# audio_spectrum.net
KiCad netlist of a schematic drawn in EAGLE
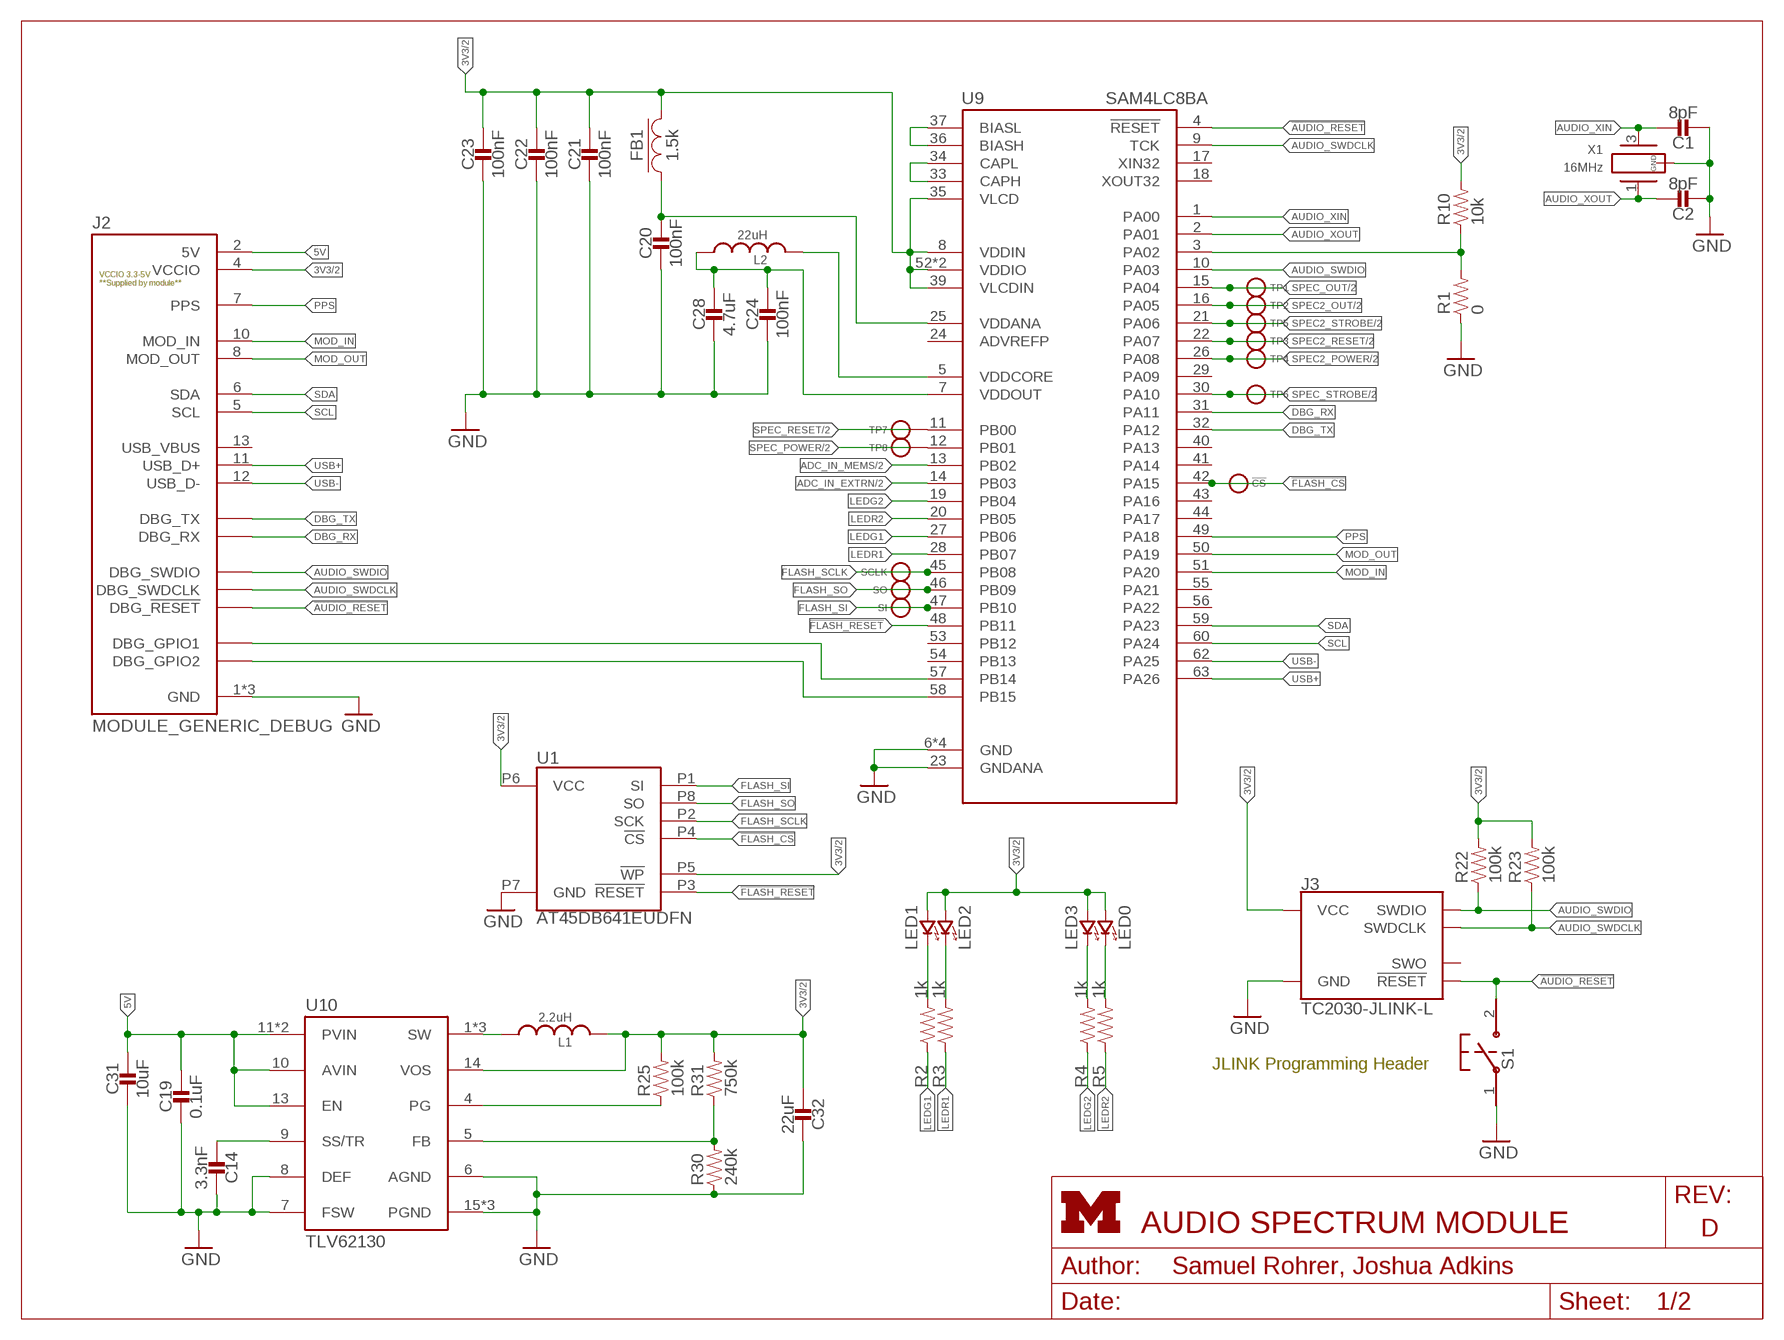
[diagram p0: schematic, sheet 1]
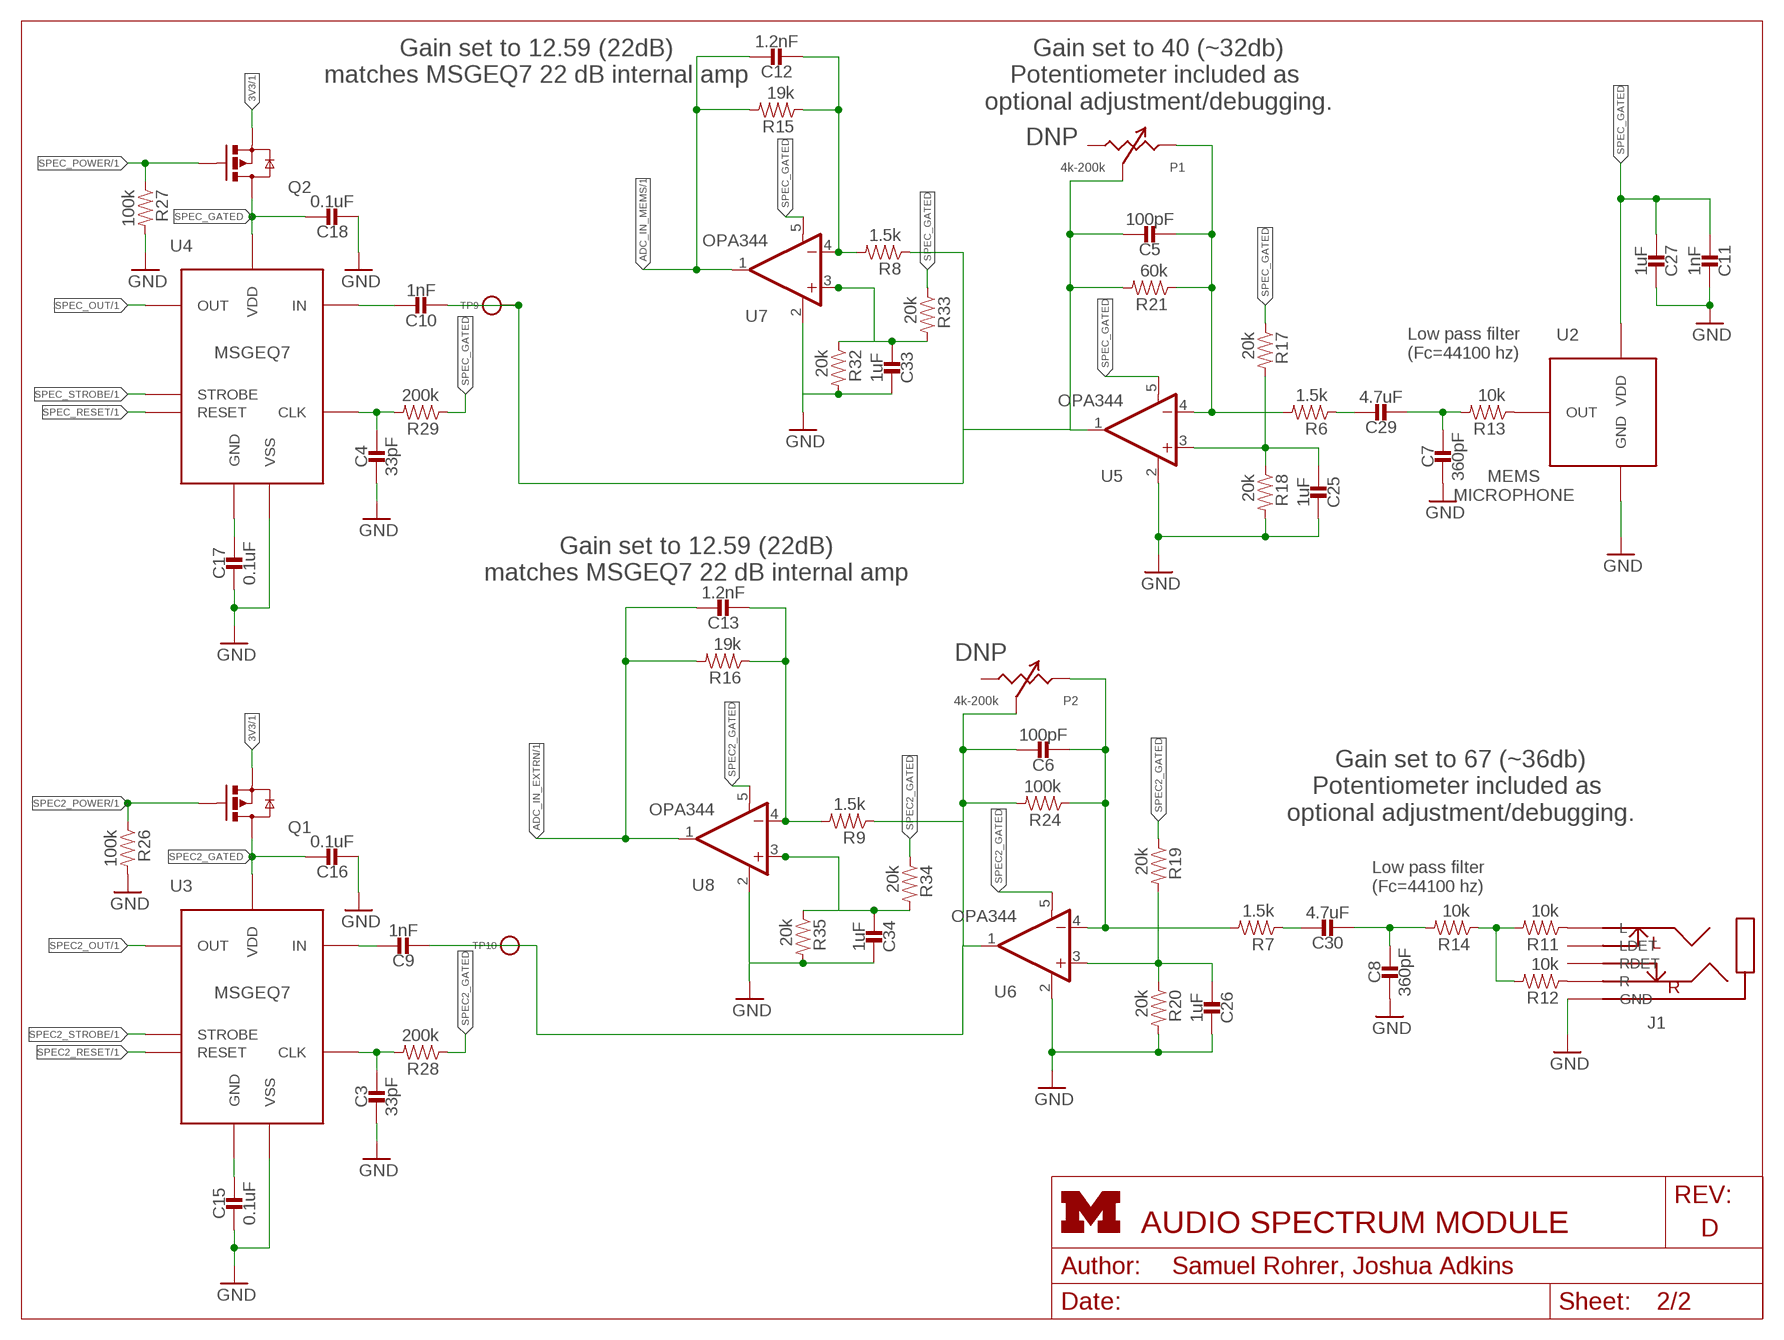
[diagram p1: schematic, sheet 2]

(export (version "E")
  (design (tool "Eeschema 10.0.6"))
  (components
    (comp (ref "C3")
      (value "33pF")
      (footprint "eagle-import:0603_CAP")
      (libsource (lib "eagle-import") (part "CAPACITOR0603_CAP"))
    )
    (comp (ref "C4")
      (value "33pF")
      (footprint "eagle-import:0603_CAP")
      (libsource (lib "eagle-import") (part "CAPACITOR0603_CAP"))
    )
    (comp (ref "C5")
      (value "100pF")
      (footprint "eagle-import:0603_CAP")
      (libsource (lib "eagle-import") (part "CAPACITOR0603_CAP"))
    )
    (comp (ref "C6")
      (value "100pF")
      (footprint "eagle-import:0603_CAP")
      (libsource (lib "eagle-import") (part "CAPACITOR0603_CAP"))
    )
    (comp (ref "C7")
      (value "360pF")
      (footprint "eagle-import:0603_CAP")
      (libsource (lib "eagle-import") (part "CAPACITOR0603_CAP"))
    )
    (comp (ref "C8")
      (value "360pF")
      (footprint "eagle-import:0603_CAP")
      (libsource (lib "eagle-import") (part "CAPACITOR0603_CAP"))
    )
    (comp (ref "C9")
      (value "1nF")
      (footprint "eagle-import:0603_CAP")
      (libsource (lib "eagle-import") (part "CAPACITOR0603_CAP"))
    )
    (comp (ref "C10")
      (value "1nF")
      (footprint "eagle-import:0603_CAP")
      (libsource (lib "eagle-import") (part "CAPACITOR0603_CAP"))
    )
    (comp (ref "C11")
      (value "1nF")
      (footprint "eagle-import:0603_CAP")
      (libsource (lib "eagle-import") (part "CAPACITOR0603_CAP"))
    )
    (comp (ref "C12")
      (value "1.2nF")
      (footprint "eagle-import:0603_CAP")
      (libsource (lib "eagle-import") (part "CAPACITOR0603_CAP"))
    )
    (comp (ref "C13")
      (value "1.2nF")
      (footprint "eagle-import:0603_CAP")
      (libsource (lib "eagle-import") (part "CAPACITOR0603_CAP"))
    )
    (comp (ref "C15")
      (value "0.1uF")
      (footprint "eagle-import:0603_CAP")
      (libsource (lib "eagle-import") (part "CAPACITOR0603_CAP"))
    )
    (comp (ref "C16")
      (value "0.1uF")
      (footprint "eagle-import:0603_CAP")
      (libsource (lib "eagle-import") (part "CAPACITOR0603_CAP"))
    )
    (comp (ref "C17")
      (value "0.1uF")
      (footprint "eagle-import:0603_CAP")
      (libsource (lib "eagle-import") (part "CAPACITOR0603_CAP"))
    )
    (comp (ref "C18")
      (value "0.1uF")
      (footprint "eagle-import:0603_CAP")
      (libsource (lib "eagle-import") (part "CAPACITOR0603_CAP"))
    )
    (comp (ref "C25")
      (value "1uF")
      (footprint "eagle-import:0603_CAP")
      (libsource (lib "eagle-import") (part "CAPACITOR0603_CAP"))
    )
    (comp (ref "C26")
      (value "1uF")
      (footprint "eagle-import:0603_CAP")
      (libsource (lib "eagle-import") (part "CAPACITOR0603_CAP"))
    )
    (comp (ref "C27")
      (value "1uF")
      (footprint "eagle-import:0603_CAP")
      (libsource (lib "eagle-import") (part "CAPACITOR0603_CAP"))
    )
    (comp (ref "C29")
      (value "4.7uF")
      (footprint "eagle-import:0603_CAP")
      (libsource (lib "eagle-import") (part "CAPACITOR0603_CAP"))
    )
    (comp (ref "C30")
      (value "4.7uF")
      (footprint "eagle-import:0603_CAP")
      (libsource (lib "eagle-import") (part "CAPACITOR0603_CAP"))
    )
    (comp (ref "C33")
      (value "1uF")
      (footprint "eagle-import:0603_CAP")
      (libsource (lib "eagle-import") (part "CAPACITOR0603_CAP"))
    )
    (comp (ref "C34")
      (value "1uF")
      (footprint "eagle-import:0603_CAP")
      (libsource (lib "eagle-import") (part "CAPACITOR0603_CAP"))
    )
    (comp (ref "J1")
      (value "AUDIO-JACK-VERTICAL")
      (footprint "eagle-import:AUDIO-JACK-VERTICAL")
      (libsource (lib "eagle-import") (part "AUDIO-JACK-VERTICAL"))
    )
    (comp (ref "P1")
      (value "4k-200k")
      (footprint "eagle-import:TC33X-2")
      (libsource (lib "eagle-import") (part "POTTC33X"))
    )
    (comp (ref "P2")
      (value "4k-200k")
      (footprint "eagle-import:TC33X-2")
      (libsource (lib "eagle-import") (part "POTTC33X"))
    )
    (comp (ref "Q1")
      (value "NX3008PBK")
      (footprint "eagle-import:SOT23-3")
      (libsource (lib "eagle-import") (part "NX3008PBK"))
    )
    (comp (ref "Q2")
      (value "NX3008PBK")
      (footprint "eagle-import:SOT23-3")
      (libsource (lib "eagle-import") (part "NX3008PBK"))
    )
    (comp (ref "R6")
      (value "1.5k")
      (footprint "eagle-import:0603-RES")
      (libsource (lib "eagle-import") (part "RESISTOR0603_RES"))
    )
    (comp (ref "R7")
      (value "1.5k")
      (footprint "eagle-import:0603-RES")
      (libsource (lib "eagle-import") (part "RESISTOR0603_RES"))
    )
    (comp (ref "R8")
      (value "1.5k")
      (footprint "eagle-import:0603-RES")
      (libsource (lib "eagle-import") (part "RESISTOR0603_RES"))
    )
    (comp (ref "R9")
      (value "1.5k")
      (footprint "eagle-import:0603-RES")
      (libsource (lib "eagle-import") (part "RESISTOR0603_RES"))
    )
    (comp (ref "R11")
      (value "10k")
      (footprint "eagle-import:0603-RES")
      (libsource (lib "eagle-import") (part "RESISTOR0603_RES"))
    )
    (comp (ref "R12")
      (value "10k")
      (footprint "eagle-import:0603-RES")
      (libsource (lib "eagle-import") (part "RESISTOR0603_RES"))
    )
    (comp (ref "R13")
      (value "10k")
      (footprint "eagle-import:0603-RES")
      (libsource (lib "eagle-import") (part "RESISTOR0603_RES"))
    )
    (comp (ref "R14")
      (value "10k")
      (footprint "eagle-import:0603-RES")
      (libsource (lib "eagle-import") (part "RESISTOR0603_RES"))
    )
    (comp (ref "R15")
      (value "19k")
      (footprint "eagle-import:0603-RES")
      (libsource (lib "eagle-import") (part "RESISTOR0603_RES"))
    )
    (comp (ref "R16")
      (value "19k")
      (footprint "eagle-import:0603-RES")
      (libsource (lib "eagle-import") (part "RESISTOR0603_RES"))
    )
    (comp (ref "R17")
      (value "20k")
      (footprint "eagle-import:0603-RES")
      (libsource (lib "eagle-import") (part "RESISTOR0603_RES"))
    )
    (comp (ref "R18")
      (value "20k")
      (footprint "eagle-import:0603-RES")
      (libsource (lib "eagle-import") (part "RESISTOR0603_RES"))
    )
    (comp (ref "R19")
      (value "20k")
      (footprint "eagle-import:0603-RES")
      (libsource (lib "eagle-import") (part "RESISTOR0603_RES"))
    )
    (comp (ref "R20")
      (value "20k")
      (footprint "eagle-import:0603-RES")
      (libsource (lib "eagle-import") (part "RESISTOR0603_RES"))
    )
    (comp (ref "R21")
      (value "60k")
      (footprint "eagle-import:0603-RES")
      (libsource (lib "eagle-import") (part "RESISTOR0603_RES"))
    )
    (comp (ref "R24")
      (value "100k")
      (footprint "eagle-import:0603-RES")
      (libsource (lib "eagle-import") (part "RESISTOR0603_RES"))
    )
    (comp (ref "R26")
      (value "100k")
      (footprint "eagle-import:0603-RES")
      (libsource (lib "eagle-import") (part "RESISTOR0603_RES"))
    )
    (comp (ref "R27")
      (value "100k")
      (footprint "eagle-import:0603-RES")
      (libsource (lib "eagle-import") (part "RESISTOR0603_RES"))
    )
    (comp (ref "R28")
      (value "200k")
      (footprint "eagle-import:0603-RES")
      (libsource (lib "eagle-import") (part "RESISTOR0603_RES"))
    )
    (comp (ref "R29")
      (value "200k")
      (footprint "eagle-import:0603-RES")
      (libsource (lib "eagle-import") (part "RESISTOR0603_RES"))
    )
    (comp (ref "R32")
      (value "20k")
      (footprint "eagle-import:0603-RES")
      (libsource (lib "eagle-import") (part "RESISTOR0603_RES"))
    )
    (comp (ref "R33")
      (value "20k")
      (footprint "eagle-import:0603-RES")
      (libsource (lib "eagle-import") (part "RESISTOR0603_RES"))
    )
    (comp (ref "R34")
      (value "20k")
      (footprint "eagle-import:0603-RES")
      (libsource (lib "eagle-import") (part "RESISTOR0603_RES"))
    )
    (comp (ref "R35")
      (value "20k")
      (footprint "eagle-import:0603-RES")
      (libsource (lib "eagle-import") (part "RESISTOR0603_RES"))
    )
    (comp (ref "TP9")
      (value "TEST_POINT_0.040IN")
      (footprint "eagle-import:TESTPOINT_0.040IN")
      (libsource (lib "eagle-import") (part "TEST_POINT_0.040IN"))
    )
    (comp (ref "TP10")
      (value "TEST_POINT_0.040IN")
      (footprint "eagle-import:TESTPOINT_0.040IN")
      (libsource (lib "eagle-import") (part "TEST_POINT_0.040IN"))
    )
    (comp (ref "U2")
      (value "MP23AB02B")
      (footprint "eagle-import:MP23AB02B")
      (libsource (lib "eagle-import") (part "MP23AB02B"))
    )
    (comp (ref "U3")
      (value "MSGEQ7")
      (footprint "eagle-import:DIP-8")
      (libsource (lib "eagle-import") (part "MSGEQ7"))
    )
    (comp (ref "U4")
      (value "MSGEQ7")
      (footprint "eagle-import:DIP-8")
      (libsource (lib "eagle-import") (part "MSGEQ7"))
    )
    (comp (ref "U5")
      (value "OPA344")
      (footprint "eagle-import:SOT23-5")
      (libsource (lib "eagle-import") (part "OPA344"))
    )
    (comp (ref "U6")
      (value "OPA344")
      (footprint "eagle-import:SOT23-5")
      (libsource (lib "eagle-import") (part "OPA344"))
    )
    (comp (ref "U7")
      (value "OPA344")
      (footprint "eagle-import:SOT23-5")
      (libsource (lib "eagle-import") (part "OPA344"))
    )
    (comp (ref "U8")
      (value "OPA344")
      (footprint "eagle-import:SOT23-5")
      (libsource (lib "eagle-import") (part "OPA344"))
    )
    (comp (ref "!CS")
      (value "TEST_POINT_0.040IN")
      (footprint "eagle-import:TESTPOINT_0.040IN")
      (libsource (lib "eagle-import") (part "TEST_POINT_0.040IN"))
    )
    (comp (ref "C1")
      (value "8pF")
      (footprint "eagle-import:0402_CAP")
      (libsource (lib "eagle-import") (part "CAPACITOR0402_CAP"))
    )
    (comp (ref "C2")
      (value "8pF")
      (footprint "eagle-import:0402_CAP")
      (libsource (lib "eagle-import") (part "CAPACITOR0402_CAP"))
    )
    (comp (ref "C14")
      (value "3.3nF")
      (footprint "eagle-import:0603_CAP")
      (libsource (lib "eagle-import") (part "CAPACITOR0603_CAP"))
    )
    (comp (ref "C19")
      (value "0.1uF")
      (footprint "eagle-import:0603_CAP")
      (libsource (lib "eagle-import") (part "CAPACITOR0603_CAP"))
    )
    (comp (ref "C20")
      (value "100nF")
      (footprint "eagle-import:0603_CAP")
      (libsource (lib "eagle-import") (part "CAPACITOR0603_CAP"))
    )
    (comp (ref "C21")
      (value "100nF")
      (footprint "eagle-import:0603_CAP")
      (libsource (lib "eagle-import") (part "CAPACITOR0603_CAP"))
    )
    (comp (ref "C22")
      (value "100nF")
      (footprint "eagle-import:0603_CAP")
      (libsource (lib "eagle-import") (part "CAPACITOR0603_CAP"))
    )
    (comp (ref "C23")
      (value "100nF")
      (footprint "eagle-import:0603_CAP")
      (libsource (lib "eagle-import") (part "CAPACITOR0603_CAP"))
    )
    (comp (ref "C24")
      (value "100nF")
      (footprint "eagle-import:0402_CAP")
      (libsource (lib "eagle-import") (part "CAPACITOR0402_CAP"))
    )
    (comp (ref "C28")
      (value "4.7uF")
      (footprint "eagle-import:0402_CAP")
      (libsource (lib "eagle-import") (part "CAPACITOR0402_CAP"))
    )
    (comp (ref "C31")
      (value "10uF")
      (footprint "eagle-import:0603_CAP")
      (libsource (lib "eagle-import") (part "CAPACITOR0603_CAP"))
    )
    (comp (ref "C32")
      (value "22uF")
      (footprint "eagle-import:0603_CAP")
      (libsource (lib "eagle-import") (part "CAPACITOR0603_CAP"))
    )
    (comp (ref "FB1")
      (value "1.5k")
      (footprint "eagle-import:0402_CAP")
      (libsource (lib "eagle-import") (part "FERRITE_BEAD0402"))
    )
    (comp (ref "J2")
      (value "MODULE_GENERIC_DEBUG")
      (footprint "eagle-import:MODULE_GENERIC_DEBUG")
      (libsource (lib "eagle-import") (part "MODULE_GENERIC_DEBUG"))
    )
    (comp (ref "J3")
      (value "TC2030-JLINK-L")
      (footprint "eagle-import:TC2030-IDC")
      (libsource (lib "eagle-import") (part "TC2030-JLINK-L"))
    )
    (comp (ref "L1")
      (value "2.2uH")
      (footprint "eagle-import:IHL-1212BZ-11")
      (libsource (lib "eagle-import") (part "INDUCTORIHL"))
    )
    (comp (ref "L2")
      (value "22uH")
      (footprint "eagle-import:1212")
      (libsource (lib "eagle-import") (part "LHQ3NP"))
    )
    (comp (ref "LED0")
      (value "LED0603")
      (footprint "eagle-import:LED-0603")
      (libsource (lib "eagle-import") (part "LED0603"))
    )
    (comp (ref "LED1")
      (value "LED0603")
      (footprint "eagle-import:LED-0603")
      (libsource (lib "eagle-import") (part "LED0603"))
    )
    (comp (ref "LED2")
      (value "LED0603")
      (footprint "eagle-import:LED-0603")
      (libsource (lib "eagle-import") (part "LED0603"))
    )
    (comp (ref "LED3")
      (value "LED0603")
      (footprint "eagle-import:LED-0603")
      (libsource (lib "eagle-import") (part "LED0603"))
    )
    (comp (ref "R1")
      (value "0")
      (footprint "eagle-import:0603-RES")
      (libsource (lib "eagle-import") (part "RESISTOR0603_RES"))
    )
    (comp (ref "R2")
      (value "1k")
      (footprint "eagle-import:0603-RES")
      (libsource (lib "eagle-import") (part "RESISTOR0603_RES"))
    )
    (comp (ref "R3")
      (value "1k")
      (footprint "eagle-import:0603-RES")
      (libsource (lib "eagle-import") (part "RESISTOR0603_RES"))
    )
    (comp (ref "R4")
      (value "1k")
      (footprint "eagle-import:0603-RES")
      (libsource (lib "eagle-import") (part "RESISTOR0603_RES"))
    )
    (comp (ref "R5")
      (value "1k")
      (footprint "eagle-import:0603-RES")
      (libsource (lib "eagle-import") (part "RESISTOR0603_RES"))
    )
    (comp (ref "R10")
      (value "10k")
      (footprint "eagle-import:0603-RES")
      (libsource (lib "eagle-import") (part "RESISTOR0603_RES"))
    )
    (comp (ref "R22")
      (value "100k")
      (footprint "eagle-import:0603-RES")
      (libsource (lib "eagle-import") (part "RESISTOR0603_RES"))
    )
    (comp (ref "R23")
      (value "100k")
      (footprint "eagle-import:0603-RES")
      (libsource (lib "eagle-import") (part "RESISTOR0603_RES"))
    )
    (comp (ref "R25")
      (value "100k")
      (footprint "eagle-import:0603-RES")
      (libsource (lib "eagle-import") (part "RESISTOR0603_RES"))
    )
    (comp (ref "R30")
      (value "240k")
      (footprint "eagle-import:0603-RES")
      (libsource (lib "eagle-import") (part "RESISTOR0603_RES"))
    )
    (comp (ref "R31")
      (value "750k")
      (footprint "eagle-import:0603-RES")
      (libsource (lib "eagle-import") (part "RESISTOR0603_RES"))
    )
    (comp (ref "S1")
      (value "B3U-1000P")
      (footprint "eagle-import:B3U-1000P")
      (libsource (lib "eagle-import") (part "B3U-1000P"))
    )
    (comp (ref "SCLK")
      (value "TEST_POINT_0.040IN")
      (footprint "eagle-import:TESTPOINT_0.040IN")
      (libsource (lib "eagle-import") (part "TEST_POINT_0.040IN"))
    )
    (comp (ref "SI")
      (value "TEST_POINT_0.040IN")
      (footprint "eagle-import:TESTPOINT_0.040IN")
      (libsource (lib "eagle-import") (part "TEST_POINT_0.040IN"))
    )
    (comp (ref "SO")
      (value "TEST_POINT_0.040IN")
      (footprint "eagle-import:TESTPOINT_0.040IN")
      (libsource (lib "eagle-import") (part "TEST_POINT_0.040IN"))
    )
    (comp (ref "TP1")
      (value "TEST_POINT_0.040IN")
      (footprint "eagle-import:TESTPOINT_0.040IN")
      (libsource (lib "eagle-import") (part "TEST_POINT_0.040IN"))
    )
    (comp (ref "TP2")
      (value "TEST_POINT_0.040IN")
      (footprint "eagle-import:TESTPOINT_0.040IN")
      (libsource (lib "eagle-import") (part "TEST_POINT_0.040IN"))
    )
    (comp (ref "TP3")
      (value "TEST_POINT_0.040IN")
      (footprint "eagle-import:TESTPOINT_0.040IN")
      (libsource (lib "eagle-import") (part "TEST_POINT_0.040IN"))
    )
    (comp (ref "TP4")
      (value "TEST_POINT_0.040IN")
      (footprint "eagle-import:TESTPOINT_0.040IN")
      (libsource (lib "eagle-import") (part "TEST_POINT_0.040IN"))
    )
    (comp (ref "TP5")
      (value "TEST_POINT_0.040IN")
      (footprint "eagle-import:TESTPOINT_0.040IN")
      (libsource (lib "eagle-import") (part "TEST_POINT_0.040IN"))
    )
    (comp (ref "TP6")
      (value "TEST_POINT_0.040IN")
      (footprint "eagle-import:TESTPOINT_0.040IN")
      (libsource (lib "eagle-import") (part "TEST_POINT_0.040IN"))
    )
    (comp (ref "TP7")
      (value "TEST_POINT_0.040IN")
      (footprint "eagle-import:TESTPOINT_0.040IN")
      (libsource (lib "eagle-import") (part "TEST_POINT_0.040IN"))
    )
    (comp (ref "TP8")
      (value "TEST_POINT_0.040IN")
      (footprint "eagle-import:TESTPOINT_0.040IN")
      (libsource (lib "eagle-import") (part "TEST_POINT_0.040IN"))
    )
    (comp (ref "U1")
      (value "AT45DB641EUDFN")
      (footprint "eagle-import:UDFN-8-5MMX6MM")
      (libsource (lib "eagle-import") (part "AT45DB641EUDFN"))
    )
    (comp (ref "U9")
      (value "SAM4LC8BA")
      (footprint "eagle-import:QFN-64-9MM")
      (libsource (lib "eagle-import") (part "SAM4LC8BA"))
    )
    (comp (ref "U10")
      (value "TLV62130")
      (footprint "eagle-import:TQFN-16_3MM")
      (libsource (lib "eagle-import") (part "TLV62130"))
    )
    (comp (ref "X1")
      (value "16MHz")
      (footprint "eagle-import:FHXXX")
      (libsource (lib "eagle-import") (part "FH1600015"))
    )
  )
  (nets
    (net (code "1") (name "3V3") (class "Default")
      (node (ref "C21") (pin "1") (pinfunction "1_1") (pintype "bidirectional"))
      (node (ref "C22") (pin "1") (pinfunction "1_1") (pintype "bidirectional"))
      (node (ref "C23") (pin "1") (pinfunction "1_1") (pintype "bidirectional"))
      (node (ref "C32") (pin "2") (pinfunction "2_2") (pintype "bidirectional"))
      (node (ref "FB1") (pin "2") (pinfunction "P$2_2") (pintype "bidirectional"))
      (node (ref "J2") (pin "4") (pinfunction "VCCIO_4") (pintype "bidirectional"))
      (node (ref "J3") (pin "1") (pinfunction "VCC_1") (pintype "bidirectional"))
      (node (ref "L1") (pin "P$2") (pinfunction "2_P$2") (pintype "bidirectional"))
      (node (ref "LED0") (pin "A") (pinfunction "ANODE_A") (pintype "bidirectional"))
      (node (ref "LED1") (pin "A") (pinfunction "ANODE_A") (pintype "bidirectional"))
      (node (ref "LED2") (pin "A") (pinfunction "ANODE_A") (pintype "bidirectional"))
      (node (ref "LED3") (pin "A") (pinfunction "ANODE_A") (pintype "bidirectional"))
      (node (ref "Q1") (pin "2") (pinfunction "S_2") (pintype "passive"))
      (node (ref "Q2") (pin "2") (pinfunction "S_2") (pintype "passive"))
      (node (ref "R10") (pin "2") (pinfunction "2_2") (pintype "passive"))
      (node (ref "R22") (pin "2") (pinfunction "2_2") (pintype "passive"))
      (node (ref "R23") (pin "2") (pinfunction "2_2") (pintype "passive"))
      (node (ref "R25") (pin "2") (pinfunction "2_2") (pintype "passive"))
      (node (ref "R31") (pin "2") (pinfunction "2_2") (pintype "passive"))
      (node (ref "U1") (pin "P5") (pinfunction "~{WP}_P5") (pintype "bidirectional"))
      (node (ref "U1") (pin "P6") (pinfunction "VCC_P6") (pintype "bidirectional"))
      (node (ref "U10") (pin "14") (pinfunction "VOS_14") (pintype "bidirectional"))
      (node (ref "U9") (pin "35") (pinfunction "VLCD_35") (pintype "bidirectional"))
      (node (ref "U9") (pin "39") (pinfunction "VLCDIN_39") (pintype "power_in"))
      (node (ref "U9") (pin "52") (pinfunction "VDDIO_52") (pintype "power_in"))
      (node (ref "U9") (pin "61") (pinfunction "VDDIO_61") (pintype "power_in"))
      (node (ref "U9") (pin "8") (pinfunction "VDDIN_8") (pintype "power_in"))
    )
    (net (code "2") (name "5V") (class "Default")
      (node (ref "C19") (pin "1") (pinfunction "1_1") (pintype "bidirectional"))
      (node (ref "C31") (pin "1") (pinfunction "1_1") (pintype "bidirectional"))
      (node (ref "J2") (pin "2") (pinfunction "5V_2") (pintype "bidirectional"))
      (node (ref "U10") (pin "10") (pinfunction "AVIN_10") (pintype "bidirectional"))
      (node (ref "U10") (pin "11") (pinfunction "PVIN_11") (pintype "bidirectional"))
      (node (ref "U10") (pin "12") (pinfunction "PVIN_12") (pintype "bidirectional"))
      (node (ref "U10") (pin "13") (pinfunction "EN_13") (pintype "bidirectional"))
    )
    (net (code "3") (name "ADC_IN_EXTRN") (class "Default")
      (node (ref "C13") (pin "1") (pinfunction "1_1") (pintype "bidirectional"))
      (node (ref "R16") (pin "2") (pinfunction "2_2") (pintype "passive"))
      (node (ref "U8") (pin "1") (pinfunction "OUT_1") (pintype "output"))
      (node (ref "U9") (pin "14") (pinfunction "PB03_14") (pintype "bidirectional"))
    )
    (net (code "4") (name "ADC_IN_MEMS") (class "Default")
      (node (ref "C12") (pin "1") (pinfunction "1_1") (pintype "bidirectional"))
      (node (ref "R15") (pin "2") (pinfunction "2_2") (pintype "passive"))
      (node (ref "U7") (pin "1") (pinfunction "OUT_1") (pintype "output"))
      (node (ref "U9") (pin "13") (pinfunction "PB02_13") (pintype "bidirectional"))
    )
    (net (code "5") (name "AUDIO_SWDCLK") (class "Default")
      (node (ref "J2") (pin "21") (pinfunction "DBG_SWDCLK_21") (pintype "bidirectional"))
      (node (ref "J3") (pin "4") (pinfunction "SWDCLK_4") (pintype "bidirectional"))
      (node (ref "R23") (pin "1") (pinfunction "1_1") (pintype "passive"))
      (node (ref "U9") (pin "9") (pinfunction "TCK_9") (pintype "bidirectional"))
    )
    (net (code "6") (name "AUDIO_SWDIO") (class "Default")
      (node (ref "J2") (pin "22") (pinfunction "DBG_SWDIO_22") (pintype "bidirectional"))
      (node (ref "J3") (pin "2") (pinfunction "SWDIO_2") (pintype "bidirectional"))
      (node (ref "R22") (pin "1") (pinfunction "1_1") (pintype "passive"))
      (node (ref "U9") (pin "10") (pinfunction "PA03_10") (pintype "bidirectional"))
    )
    (net (code "7") (name "AUDIO_XIN") (class "Default")
      (node (ref "C1") (pin "1") (pinfunction "1_1") (pintype "bidirectional"))
      (node (ref "U9") (pin "1") (pinfunction "PA00_1") (pintype "bidirectional"))
      (node (ref "X1") (pin "3") (pinfunction "2_3") (pintype "bidirectional"))
    )
    (net (code "8") (name "AUDIO_XOUT") (class "Default")
      (node (ref "C2") (pin "1") (pinfunction "1_1") (pintype "bidirectional"))
      (node (ref "U9") (pin "2") (pinfunction "PA01_2") (pintype "bidirectional"))
      (node (ref "X1") (pin "1") (pinfunction "1_1") (pintype "bidirectional"))
    )
    (net (code "9") (name "DBG_RX") (class "Default")
      (node (ref "J2") (pin "18") (pinfunction "DBG_RX_18") (pintype "bidirectional"))
      (node (ref "U9") (pin "31") (pinfunction "PA11_31") (pintype "bidirectional"))
    )
    (net (code "10") (name "DBG_TX") (class "Default")
      (node (ref "J2") (pin "17") (pinfunction "DBG_TX_17") (pintype "bidirectional"))
      (node (ref "U9") (pin "32") (pinfunction "PA12_32") (pintype "bidirectional"))
    )
    (net (code "11") (name "FLASH_SCLK") (class "Default")
      (node (ref "SCLK") (pin "TESTPOINT") (pinfunction "TESTPOINT_TESTPOINT") (pintype "bidirectional"))
      (node (ref "U1") (pin "P2") (pinfunction "SCK_P2") (pintype "bidirectional"))
      (node (ref "U9") (pin "45") (pinfunction "PB08_45") (pintype "bidirectional"))
    )
    (net (code "12") (name "FLASH_SI") (class "Default")
      (node (ref "SI") (pin "TESTPOINT") (pinfunction "TESTPOINT_TESTPOINT") (pintype "bidirectional"))
      (node (ref "U1") (pin "P1") (pinfunction "SI_P1") (pintype "bidirectional"))
      (node (ref "U9") (pin "47") (pinfunction "PB10_47") (pintype "bidirectional"))
    )
    (net (code "13") (name "FLASH_SO") (class "Default")
      (node (ref "SO") (pin "TESTPOINT") (pinfunction "TESTPOINT_TESTPOINT") (pintype "bidirectional"))
      (node (ref "U1") (pin "P8") (pinfunction "SO_P8") (pintype "bidirectional"))
      (node (ref "U9") (pin "46") (pinfunction "PB09_46") (pintype "bidirectional"))
    )
    (net (code "14") (name "GND") (class "Default")
      (node (ref "C1") (pin "2") (pinfunction "2_2") (pintype "bidirectional"))
      (node (ref "C11") (pin "1") (pinfunction "1_1") (pintype "bidirectional"))
      (node (ref "C14") (pin "1") (pinfunction "1_1") (pintype "bidirectional"))
      (node (ref "C15") (pin "2") (pinfunction "2_2") (pintype "bidirectional"))
      (node (ref "C16") (pin "2") (pinfunction "2_2") (pintype "bidirectional"))
      (node (ref "C17") (pin "2") (pinfunction "2_2") (pintype "bidirectional"))
      (node (ref "C18") (pin "2") (pinfunction "2_2") (pintype "bidirectional"))
      (node (ref "C19") (pin "2") (pinfunction "2_2") (pintype "bidirectional"))
      (node (ref "C2") (pin "2") (pinfunction "2_2") (pintype "bidirectional"))
      (node (ref "C20") (pin "2") (pinfunction "2_2") (pintype "bidirectional"))
      (node (ref "C21") (pin "2") (pinfunction "2_2") (pintype "bidirectional"))
      (node (ref "C22") (pin "2") (pinfunction "2_2") (pintype "bidirectional"))
      (node (ref "C23") (pin "2") (pinfunction "2_2") (pintype "bidirectional"))
      (node (ref "C24") (pin "2") (pinfunction "2_2") (pintype "bidirectional"))
      (node (ref "C25") (pin "1") (pinfunction "1_1") (pintype "bidirectional"))
      (node (ref "C26") (pin "1") (pinfunction "1_1") (pintype "bidirectional"))
      (node (ref "C27") (pin "1") (pinfunction "1_1") (pintype "bidirectional"))
      (node (ref "C28") (pin "2") (pinfunction "2_2") (pintype "bidirectional"))
      (node (ref "C3") (pin "2") (pinfunction "2_2") (pintype "bidirectional"))
      (node (ref "C31") (pin "2") (pinfunction "2_2") (pintype "bidirectional"))
      (node (ref "C32") (pin "1") (pinfunction "1_1") (pintype "bidirectional"))
      (node (ref "C33") (pin "1") (pinfunction "1_1") (pintype "bidirectional"))
      (node (ref "C34") (pin "1") (pinfunction "1_1") (pintype "bidirectional"))
      (node (ref "C4") (pin "2") (pinfunction "2_2") (pintype "bidirectional"))
      (node (ref "C7") (pin "2") (pinfunction "2_2") (pintype "bidirectional"))
      (node (ref "C8") (pin "2") (pinfunction "2_2") (pintype "bidirectional"))
      (node (ref "J1") (pin "5") (pinfunction "GND_5") (pintype "bidirectional"))
      (node (ref "J2") (pin "1") (pinfunction "GND_1") (pintype "bidirectional"))
      (node (ref "J2") (pin "14") (pinfunction "GND_14") (pintype "bidirectional"))
      (node (ref "J2") (pin "15") (pinfunction "GND_15") (pintype "bidirectional"))
      (node (ref "J3") (pin "5") (pinfunction "GND_5") (pintype "bidirectional"))
      (node (ref "R1") (pin "1") (pinfunction "1_1") (pintype "passive"))
      (node (ref "R18") (pin "2") (pinfunction "2_2") (pintype "passive"))
      (node (ref "R20") (pin "2") (pinfunction "2_2") (pintype "passive"))
      (node (ref "R26") (pin "2") (pinfunction "2_2") (pintype "passive"))
      (node (ref "R27") (pin "2") (pinfunction "2_2") (pintype "passive"))
      (node (ref "R30") (pin "1") (pinfunction "1_1") (pintype "passive"))
      (node (ref "R32") (pin "2") (pinfunction "2_2") (pintype "passive"))
      (node (ref "R35") (pin "2") (pinfunction "2_2") (pintype "passive"))
      (node (ref "S1") (pin "1") (pinfunction "P$1_1") (pintype "passive"))
      (node (ref "U1") (pin "P7") (pinfunction "GND_P7") (pintype "bidirectional"))
      (node (ref "U10") (pin "15") (pinfunction "PGND_15") (pintype "bidirectional"))
      (node (ref "U10") (pin "16") (pinfunction "PGND_16") (pintype "bidirectional"))
      (node (ref "U10") (pin "6") (pinfunction "AGND_6") (pintype "bidirectional"))
      (node (ref "U10") (pin "7") (pinfunction "FSW_7") (pintype "bidirectional"))
      (node (ref "U10") (pin "8") (pinfunction "DEF_8") (pintype "bidirectional"))
      (node (ref "U10") (pin "GND") (pinfunction "PGND_GND") (pintype "bidirectional"))
      (node (ref "U2") (pin "3") (pinfunction "GND_3") (pintype "bidirectional"))
      (node (ref "U3") (pin "2") (pinfunction "VSS_2") (pintype "bidirectional"))
      (node (ref "U4") (pin "2") (pinfunction "VSS_2") (pintype "bidirectional"))
      (node (ref "U5") (pin "2") (pinfunction "V-_2") (pintype "power_in"))
      (node (ref "U6") (pin "2") (pinfunction "V-_2") (pintype "power_in"))
      (node (ref "U7") (pin "2") (pinfunction "V-_2") (pintype "power_in"))
      (node (ref "U8") (pin "2") (pinfunction "V-_2") (pintype "power_in"))
      (node (ref "U9") (pin "23") (pinfunction "GNDANA_23") (pintype "power_in"))
      (node (ref "U9") (pin "38") (pinfunction "GND_38") (pintype "power_in"))
      (node (ref "U9") (pin "6") (pinfunction "GND_6") (pintype "power_in"))
      (node (ref "U9") (pin "64") (pinfunction "GND_64") (pintype "power_in"))
      (node (ref "U9") (pin "GND") (pinfunction "GND_GND") (pintype "power_in"))
      (node (ref "X1") (pin "2") (pinfunction "GND_2") (pintype "bidirectional"))
      (node (ref "X1") (pin "4") (pinfunction "GND_4") (pintype "bidirectional"))
    )
    (net (code "15") (name "LEDG1") (class "Default")
      (node (ref "R2") (pin "1") (pinfunction "1_1") (pintype "passive"))
      (node (ref "U9") (pin "27") (pinfunction "PB06_27") (pintype "bidirectional"))
    )
    (net (code "16") (name "LEDG2") (class "Default")
      (node (ref "R4") (pin "1") (pinfunction "1_1") (pintype "passive"))
      (node (ref "U9") (pin "19") (pinfunction "PB04_19") (pintype "bidirectional"))
    )
    (net (code "17") (name "LEDR1") (class "Default")
      (node (ref "R3") (pin "1") (pinfunction "1_1") (pintype "passive"))
      (node (ref "U9") (pin "28") (pinfunction "PB07_28") (pintype "bidirectional"))
    )
    (net (code "18") (name "LEDR2") (class "Default")
      (node (ref "R5") (pin "1") (pinfunction "1_1") (pintype "passive"))
      (node (ref "U9") (pin "20") (pinfunction "PB05_20") (pintype "bidirectional"))
    )
    (net (code "19") (name "MOD_IN") (class "Default")
      (node (ref "J2") (pin "10") (pinfunction "MOD_IN_10") (pintype "bidirectional"))
      (node (ref "U9") (pin "51") (pinfunction "PA20_51") (pintype "bidirectional"))
    )
    (net (code "20") (name "MOD_OUT") (class "Default")
      (node (ref "J2") (pin "8") (pinfunction "MOD_OUT_8") (pintype "bidirectional"))
      (node (ref "U9") (pin "50") (pinfunction "PA19_50") (pintype "bidirectional"))
    )
    (net (code "21") (name "Net-(C29-Pad1)") (class "Default")
      (node (ref "C29") (pin "1") (pinfunction "1_1") (pintype "bidirectional"))
      (node (ref "R6") (pin "1") (pinfunction "1_1") (pintype "passive"))
    )
    (net (code "22") (name "Net-(C29-Pad2)") (class "Default")
      (node (ref "C29") (pin "2") (pinfunction "2_2") (pintype "bidirectional"))
      (node (ref "C7") (pin "1") (pinfunction "1_1") (pintype "bidirectional"))
      (node (ref "R13") (pin "2") (pinfunction "2_2") (pintype "passive"))
    )
    (net (code "23") (name "Net-(C30-Pad1)") (class "Default")
      (node (ref "C30") (pin "1") (pinfunction "1_1") (pintype "bidirectional"))
      (node (ref "R7") (pin "1") (pinfunction "1_1") (pintype "passive"))
    )
    (net (code "24") (name "Net-(C30-Pad2)") (class "Default")
      (node (ref "C30") (pin "2") (pinfunction "2_2") (pintype "bidirectional"))
      (node (ref "C8") (pin "1") (pinfunction "1_1") (pintype "bidirectional"))
      (node (ref "R14") (pin "2") (pinfunction "2_2") (pintype "passive"))
    )
    (net (code "25") (name "Net-(FB1-P$1)") (class "Default")
      (node (ref "C20") (pin "1") (pinfunction "1_1") (pintype "bidirectional"))
      (node (ref "FB1") (pin "1") (pinfunction "P$1_1") (pintype "bidirectional"))
      (node (ref "U9") (pin "25") (pinfunction "VDDANA_25") (pintype "power_in"))
    )
    (net (code "26") (name "Net-(J1-L)") (class "Default")
      (node (ref "J1") (pin "4") (pinfunction "L_4") (pintype "bidirectional"))
      (node (ref "R11") (pin "1") (pinfunction "1_1") (pintype "passive"))
    )
    (net (code "27") (name "Net-(J1-R)") (class "Default")
      (node (ref "J1") (pin "1") (pinfunction "R_1") (pintype "bidirectional"))
      (node (ref "R12") (pin "1") (pinfunction "1_1") (pintype "passive"))
    )
    (net (code "28") (name "Net-(J2-DBG_GPIO1)") (class "Default")
      (node (ref "J2") (pin "16") (pinfunction "DBG_GPIO1_16") (pintype "bidirectional"))
      (node (ref "U9") (pin "57") (pinfunction "PB14_57") (pintype "bidirectional"))
    )
    (net (code "29") (name "Net-(J2-DBG_GPIO2)") (class "Default")
      (node (ref "J2") (pin "19") (pinfunction "DBG_GPIO2_19") (pintype "bidirectional"))
      (node (ref "U9") (pin "58") (pinfunction "PB15_58") (pintype "bidirectional"))
    )
    (net (code "30") (name "Net-(L1-1)") (class "Default")
      (node (ref "L1") (pin "P$1") (pinfunction "1_P$1") (pintype "bidirectional"))
      (node (ref "U10") (pin "1") (pinfunction "SW_1") (pintype "bidirectional"))
      (node (ref "U10") (pin "2") (pinfunction "SW_2") (pintype "bidirectional"))
      (node (ref "U10") (pin "3") (pinfunction "SW_3") (pintype "bidirectional"))
    )
    (net (code "31") (name "Net-(L2-1)") (class "Default")
      (node (ref "C24") (pin "1") (pinfunction "1_1") (pintype "bidirectional"))
      (node (ref "C28") (pin "1") (pinfunction "1_1") (pintype "bidirectional"))
      (node (ref "L2") (pin "P$1") (pinfunction "1_P$1") (pintype "bidirectional"))
      (node (ref "U9") (pin "7") (pinfunction "VDDOUT_7") (pintype "power_in"))
    )
    (net (code "32") (name "Net-(L2-2)") (class "Default")
      (node (ref "L2") (pin "P$2") (pinfunction "2_P$2") (pintype "bidirectional"))
      (node (ref "U9") (pin "5") (pinfunction "VDDCORE_5") (pintype "power_in"))
    )
    (net (code "33") (name "Net-(LED0-CATHODE)") (class "Default")
      (node (ref "LED0") (pin "C") (pinfunction "CATHODE_C") (pintype "bidirectional"))
      (node (ref "R5") (pin "2") (pinfunction "2_2") (pintype "passive"))
    )
    (net (code "34") (name "Net-(LED1-CATHODE)") (class "Default")
      (node (ref "LED1") (pin "C") (pinfunction "CATHODE_C") (pintype "bidirectional"))
      (node (ref "R2") (pin "2") (pinfunction "2_2") (pintype "passive"))
    )
    (net (code "35") (name "Net-(LED2-CATHODE)") (class "Default")
      (node (ref "LED2") (pin "C") (pinfunction "CATHODE_C") (pintype "bidirectional"))
      (node (ref "R3") (pin "2") (pinfunction "2_2") (pintype "passive"))
    )
    (net (code "36") (name "Net-(LED3-CATHODE)") (class "Default")
      (node (ref "LED3") (pin "C") (pinfunction "CATHODE_C") (pintype "bidirectional"))
      (node (ref "R4") (pin "2") (pinfunction "2_2") (pintype "passive"))
    )
    (net (code "37") (name "Net-(P1-CW)") (class "Default")
      (node (ref "C5") (pin "2") (pinfunction "2_2") (pintype "bidirectional"))
      (node (ref "P1") (pin "2") (pinfunction "CW_2") (pintype "bidirectional"))
      (node (ref "R21") (pin "1") (pinfunction "1_1") (pintype "passive"))
      (node (ref "R6") (pin "2") (pinfunction "2_2") (pintype "passive"))
      (node (ref "U5") (pin "4") (pinfunction "-IN_4") (pintype "input"))
    )
    (net (code "38") (name "Net-(P1-W)") (class "Default")
      (node (ref "C10") (pin "2") (pinfunction "2_2") (pintype "bidirectional"))
      (node (ref "C5") (pin "1") (pinfunction "1_1") (pintype "bidirectional"))
      (node (ref "P1") (pin "3") (pinfunction "W_3") (pintype "bidirectional"))
      (node (ref "R21") (pin "2") (pinfunction "2_2") (pintype "passive"))
      (node (ref "R8") (pin "1") (pinfunction "1_1") (pintype "passive"))
      (node (ref "TP9") (pin "TESTPOINT") (pinfunction "TESTPOINT_TESTPOINT") (pintype "bidirectional"))
      (node (ref "U5") (pin "1") (pinfunction "OUT_1") (pintype "output"))
    )
    (net (code "39") (name "Net-(P2-CW)") (class "Default")
      (node (ref "C6") (pin "2") (pinfunction "2_2") (pintype "bidirectional"))
      (node (ref "P2") (pin "2") (pinfunction "CW_2") (pintype "bidirectional"))
      (node (ref "R24") (pin "1") (pinfunction "1_1") (pintype "passive"))
      (node (ref "R7") (pin "2") (pinfunction "2_2") (pintype "passive"))
      (node (ref "U6") (pin "4") (pinfunction "-IN_4") (pintype "input"))
    )
    (net (code "40") (name "Net-(P2-W)") (class "Default")
      (node (ref "C6") (pin "1") (pinfunction "1_1") (pintype "bidirectional"))
      (node (ref "C9") (pin "2") (pinfunction "2_2") (pintype "bidirectional"))
      (node (ref "P2") (pin "3") (pinfunction "W_3") (pintype "bidirectional"))
      (node (ref "R24") (pin "2") (pinfunction "2_2") (pintype "passive"))
      (node (ref "R9") (pin "1") (pinfunction "1_1") (pintype "passive"))
      (node (ref "TP10") (pin "TESTPOINT") (pinfunction "TESTPOINT_TESTPOINT") (pintype "bidirectional"))
      (node (ref "U6") (pin "1") (pinfunction "OUT_1") (pintype "output"))
    )
    (net (code "41") (name "Net-(R11-Pad2)") (class "Default")
      (node (ref "R11") (pin "2") (pinfunction "2_2") (pintype "passive"))
      (node (ref "R12") (pin "2") (pinfunction "2_2") (pintype "passive"))
      (node (ref "R14") (pin "1") (pinfunction "1_1") (pintype "passive"))
    )
    (net (code "42") (name "Net-(U2-OUT)") (class "Default")
      (node (ref "R13") (pin "1") (pinfunction "1_1") (pintype "passive"))
      (node (ref "U2") (pin "1") (pinfunction "OUT_1") (pintype "bidirectional"))
    )
    (net (code "43") (name "Net-(U3-CLK)") (class "Default")
      (node (ref "C3") (pin "1") (pinfunction "1_1") (pintype "bidirectional"))
      (node (ref "R28") (pin "2") (pinfunction "2_2") (pintype "passive"))
      (node (ref "U3") (pin "8") (pinfunction "CLK_8") (pintype "bidirectional"))
    )
    (net (code "44") (name "Net-(U3-GND)") (class "Default")
      (node (ref "C15") (pin "1") (pinfunction "1_1") (pintype "bidirectional"))
      (node (ref "U3") (pin "6") (pinfunction "GND_6") (pintype "bidirectional"))
    )
    (net (code "45") (name "Net-(U3-IN)") (class "Default")
      (node (ref "C9") (pin "1") (pinfunction "1_1") (pintype "bidirectional"))
      (node (ref "U3") (pin "5") (pinfunction "IN_5") (pintype "bidirectional"))
    )
    (net (code "46") (name "Net-(U4-CLK)") (class "Default")
      (node (ref "C4") (pin "1") (pinfunction "1_1") (pintype "bidirectional"))
      (node (ref "R29") (pin "2") (pinfunction "2_2") (pintype "passive"))
      (node (ref "U4") (pin "8") (pinfunction "CLK_8") (pintype "bidirectional"))
    )
    (net (code "47") (name "Net-(U4-GND)") (class "Default")
      (node (ref "C17") (pin "1") (pinfunction "1_1") (pintype "bidirectional"))
      (node (ref "U4") (pin "6") (pinfunction "GND_6") (pintype "bidirectional"))
    )
    (net (code "48") (name "Net-(U4-IN)") (class "Default")
      (node (ref "C10") (pin "1") (pinfunction "1_1") (pintype "bidirectional"))
      (node (ref "U4") (pin "5") (pinfunction "IN_5") (pintype "bidirectional"))
    )
    (net (code "49") (name "Net-(U5-+IN)") (class "Default")
      (node (ref "C25") (pin "2") (pinfunction "2_2") (pintype "bidirectional"))
      (node (ref "R17") (pin "2") (pinfunction "2_2") (pintype "passive"))
      (node (ref "R18") (pin "1") (pinfunction "1_1") (pintype "passive"))
      (node (ref "U5") (pin "3") (pinfunction "+IN_3") (pintype "input"))
    )
    (net (code "50") (name "Net-(U6-+IN)") (class "Default")
      (node (ref "C26") (pin "2") (pinfunction "2_2") (pintype "bidirectional"))
      (node (ref "R19") (pin "2") (pinfunction "2_2") (pintype "passive"))
      (node (ref "R20") (pin "1") (pinfunction "1_1") (pintype "passive"))
      (node (ref "U6") (pin "3") (pinfunction "+IN_3") (pintype "input"))
    )
    (net (code "51") (name "Net-(U7-+IN)") (class "Default")
      (node (ref "C33") (pin "2") (pinfunction "2_2") (pintype "bidirectional"))
      (node (ref "R32") (pin "1") (pinfunction "1_1") (pintype "passive"))
      (node (ref "R33") (pin "2") (pinfunction "2_2") (pintype "passive"))
      (node (ref "U7") (pin "3") (pinfunction "+IN_3") (pintype "input"))
    )
    (net (code "52") (name "Net-(U7--IN)") (class "Default")
      (node (ref "C12") (pin "2") (pinfunction "2_2") (pintype "bidirectional"))
      (node (ref "R15") (pin "1") (pinfunction "1_1") (pintype "passive"))
      (node (ref "R8") (pin "2") (pinfunction "2_2") (pintype "passive"))
      (node (ref "U7") (pin "4") (pinfunction "-IN_4") (pintype "input"))
    )
    (net (code "53") (name "Net-(U8-+IN)") (class "Default")
      (node (ref "C34") (pin "2") (pinfunction "2_2") (pintype "bidirectional"))
      (node (ref "R34") (pin "2") (pinfunction "2_2") (pintype "passive"))
      (node (ref "R35") (pin "1") (pinfunction "1_1") (pintype "passive"))
      (node (ref "U8") (pin "3") (pinfunction "+IN_3") (pintype "input"))
    )
    (net (code "54") (name "Net-(U8--IN)") (class "Default")
      (node (ref "C13") (pin "2") (pinfunction "2_2") (pintype "bidirectional"))
      (node (ref "R16") (pin "1") (pinfunction "1_1") (pintype "passive"))
      (node (ref "R9") (pin "2") (pinfunction "2_2") (pintype "passive"))
      (node (ref "U8") (pin "4") (pinfunction "-IN_4") (pintype "input"))
    )
    (net (code "55") (name "Net-(U9-BIASH)") (class "Default")
      (node (ref "U9") (pin "36") (pinfunction "BIASH_36") (pintype "bidirectional"))
      (node (ref "U9") (pin "37") (pinfunction "BIASL_37") (pintype "bidirectional"))
    )
    (net (code "56") (name "Net-(U9-CAPH)") (class "Default")
      (node (ref "U9") (pin "33") (pinfunction "CAPH_33") (pintype "bidirectional"))
      (node (ref "U9") (pin "34") (pinfunction "CAPL_34") (pintype "bidirectional"))
    )
    (net (code "57") (name "Net-(U9-PA02)") (class "Default")
      (node (ref "R1") (pin "2") (pinfunction "2_2") (pintype "passive"))
      (node (ref "R10") (pin "1") (pinfunction "1_1") (pintype "passive"))
      (node (ref "U9") (pin "3") (pinfunction "PA02_3") (pintype "bidirectional"))
    )
    (net (code "58") (name "Net-(U9-PB00)") (class "Default")
      (node (ref "TP7") (pin "TESTPOINT") (pinfunction "TESTPOINT_TESTPOINT") (pintype "bidirectional"))
      (node (ref "U9") (pin "11") (pinfunction "PB00_11") (pintype "bidirectional"))
    )
    (net (code "59") (name "Net-(U9-PB01)") (class "Default")
      (node (ref "TP8") (pin "TESTPOINT") (pinfunction "TESTPOINT_TESTPOINT") (pintype "bidirectional"))
      (node (ref "U9") (pin "12") (pinfunction "PB01_12") (pintype "bidirectional"))
    )
    (net (code "60") (name "Net-(U10-FB)") (class "Default")
      (node (ref "R30") (pin "2") (pinfunction "2_2") (pintype "passive"))
      (node (ref "R31") (pin "1") (pinfunction "1_1") (pintype "passive"))
      (node (ref "U10") (pin "5") (pinfunction "FB_5") (pintype "bidirectional"))
    )
    (net (code "61") (name "Net-(U10-PG)") (class "Default")
      (node (ref "R25") (pin "1") (pinfunction "1_1") (pintype "passive"))
      (node (ref "U10") (pin "4") (pinfunction "PG_4") (pintype "bidirectional"))
    )
    (net (code "62") (name "Net-(U10-SS{slash}TR)") (class "Default")
      (node (ref "C14") (pin "2") (pinfunction "2_2") (pintype "bidirectional"))
      (node (ref "U10") (pin "9") (pinfunction "SS/TR_9") (pintype "bidirectional"))
    )
    (net (code "63") (name "PPS") (class "Default")
      (node (ref "J2") (pin "7") (pinfunction "PPS_7") (pintype "bidirectional"))
      (node (ref "U9") (pin "49") (pinfunction "PA18_49") (pintype "bidirectional"))
    )
    (net (code "64") (name "SCL") (class "Default")
      (node (ref "J2") (pin "5") (pinfunction "SCL_5") (pintype "bidirectional"))
      (node (ref "U9") (pin "60") (pinfunction "PA24_60") (pintype "bidirectional"))
    )
    (net (code "65") (name "SDA") (class "Default")
      (node (ref "J2") (pin "6") (pinfunction "SDA_6") (pintype "bidirectional"))
      (node (ref "U9") (pin "59") (pinfunction "PA23_59") (pintype "bidirectional"))
    )
    (net (code "66") (name "SPEC2_GATED") (class "Default")
      (node (ref "C16") (pin "1") (pinfunction "1_1") (pintype "bidirectional"))
      (node (ref "Q1") (pin "3") (pinfunction "D_3") (pintype "passive"))
      (node (ref "R19") (pin "1") (pinfunction "1_1") (pintype "passive"))
      (node (ref "R28") (pin "1") (pinfunction "1_1") (pintype "passive"))
      (node (ref "R34") (pin "1") (pinfunction "1_1") (pintype "passive"))
      (node (ref "U3") (pin "1") (pinfunction "VDD_1") (pintype "bidirectional"))
      (node (ref "U6") (pin "5") (pinfunction "V+_5") (pintype "power_in"))
      (node (ref "U8") (pin "5") (pinfunction "V+_5") (pintype "power_in"))
    )
    (net (code "67") (name "SPEC2_OUT") (class "Default")
      (node (ref "TP2") (pin "TESTPOINT") (pinfunction "TESTPOINT_TESTPOINT") (pintype "bidirectional"))
      (node (ref "U3") (pin "3") (pinfunction "OUT_3") (pintype "bidirectional"))
      (node (ref "U9") (pin "16") (pinfunction "PA05_16") (pintype "bidirectional"))
    )
    (net (code "68") (name "SPEC2_POWER") (class "Default")
      (node (ref "Q1") (pin "1") (pinfunction "G_1") (pintype "passive"))
      (node (ref "R26") (pin "1") (pinfunction "1_1") (pintype "passive"))
      (node (ref "TP4") (pin "TESTPOINT") (pinfunction "TESTPOINT_TESTPOINT") (pintype "bidirectional"))
      (node (ref "U9") (pin "26") (pinfunction "PA08_26") (pintype "bidirectional"))
    )
    (net (code "69") (name "SPEC2_RESET") (class "Default")
      (node (ref "TP3") (pin "TESTPOINT") (pinfunction "TESTPOINT_TESTPOINT") (pintype "bidirectional"))
      (node (ref "U3") (pin "7") (pinfunction "RESET_7") (pintype "bidirectional"))
      (node (ref "U9") (pin "22") (pinfunction "PA07_22") (pintype "bidirectional"))
    )
    (net (code "70") (name "SPEC2_STROBE") (class "Default")
      (node (ref "TP5") (pin "TESTPOINT") (pinfunction "TESTPOINT_TESTPOINT") (pintype "bidirectional"))
      (node (ref "U3") (pin "4") (pinfunction "STROBE_4") (pintype "bidirectional"))
      (node (ref "U9") (pin "21") (pinfunction "PA06_21") (pintype "bidirectional"))
    )
    (net (code "71") (name "SPEC_GATED") (class "Default")
      (node (ref "C11") (pin "2") (pinfunction "2_2") (pintype "bidirectional"))
      (node (ref "C18") (pin "1") (pinfunction "1_1") (pintype "bidirectional"))
      (node (ref "C27") (pin "2") (pinfunction "2_2") (pintype "bidirectional"))
      (node (ref "Q2") (pin "3") (pinfunction "D_3") (pintype "passive"))
      (node (ref "R17") (pin "1") (pinfunction "1_1") (pintype "passive"))
      (node (ref "R29") (pin "1") (pinfunction "1_1") (pintype "passive"))
      (node (ref "R33") (pin "1") (pinfunction "1_1") (pintype "passive"))
      (node (ref "U2") (pin "2") (pinfunction "VDD_2") (pintype "bidirectional"))
      (node (ref "U4") (pin "1") (pinfunction "VDD_1") (pintype "bidirectional"))
      (node (ref "U5") (pin "5") (pinfunction "V+_5") (pintype "power_in"))
      (node (ref "U7") (pin "5") (pinfunction "V+_5") (pintype "power_in"))
    )
    (net (code "72") (name "SPEC_OUT") (class "Default")
      (node (ref "TP1") (pin "TESTPOINT") (pinfunction "TESTPOINT_TESTPOINT") (pintype "bidirectional"))
      (node (ref "U4") (pin "3") (pinfunction "OUT_3") (pintype "bidirectional"))
      (node (ref "U9") (pin "15") (pinfunction "PA04_15") (pintype "bidirectional"))
    )
    (net (code "73") (name "SPEC_POWER") (class "Default")
      (node (ref "Q2") (pin "1") (pinfunction "G_1") (pintype "passive"))
      (node (ref "R27") (pin "1") (pinfunction "1_1") (pintype "passive"))
    )
    (net (code "74") (name "SPEC_RESET") (class "Default")
      (node (ref "U4") (pin "7") (pinfunction "RESET_7") (pintype "bidirectional"))
    )
    (net (code "75") (name "SPEC_STROBE") (class "Default")
      (node (ref "TP6") (pin "TESTPOINT") (pinfunction "TESTPOINT_TESTPOINT") (pintype "bidirectional"))
      (node (ref "U4") (pin "4") (pinfunction "STROBE_4") (pintype "bidirectional"))
      (node (ref "U9") (pin "30") (pinfunction "PA10_30") (pintype "bidirectional"))
    )
    (net (code "76") (name "USB+") (class "Default")
      (node (ref "J2") (pin "11") (pinfunction "USB_D+_11") (pintype "bidirectional"))
      (node (ref "U9") (pin "63") (pinfunction "PA26_63") (pintype "bidirectional"))
    )
    (net (code "77") (name "USB-") (class "Default")
      (node (ref "J2") (pin "12") (pinfunction "USB_D-_12") (pintype "bidirectional"))
      (node (ref "U9") (pin "62") (pinfunction "PA25_62") (pintype "bidirectional"))
    )
    (net (code "78") (name "unconnected-(J1-LDET-Pad3)") (class "Default")
      (node (ref "J1") (pin "3") (pinfunction "LDET_3") (pintype "bidirectional"))
    )
    (net (code "79") (name "unconnected-(J1-RDET-Pad2)") (class "Default")
      (node (ref "J1") (pin "2") (pinfunction "RDET_2") (pintype "bidirectional"))
    )
    (net (code "80") (name "unconnected-(J2-USB_VBUS-Pad13)") (class "Default")
      (node (ref "J2") (pin "13") (pinfunction "USB_VBUS_13") (pintype "bidirectional"))
    )
    (net (code "81") (name "unconnected-(J3-SWO-Pad6)") (class "Default")
      (node (ref "J3") (pin "6") (pinfunction "SWO_6") (pintype "bidirectional"))
    )
    (net (code "82") (name "unconnected-(P1-CCW-Pad1)") (class "Default")
      (node (ref "P1") (pin "1") (pinfunction "CCW_1") (pintype "bidirectional"))
    )
    (net (code "83") (name "unconnected-(P2-CCW-Pad1)") (class "Default")
      (node (ref "P2") (pin "1") (pinfunction "CCW_1") (pintype "bidirectional"))
    )
    (net (code "84") (name "unconnected-(U9-ADVREFP-Pad24)") (class "Default")
      (node (ref "U9") (pin "24") (pinfunction "ADVREFP_24") (pintype "bidirectional"))
    )
    (net (code "85") (name "unconnected-(U9-PA09-Pad29)") (class "Default")
      (node (ref "U9") (pin "29") (pinfunction "PA09_29") (pintype "bidirectional"))
    )
    (net (code "86") (name "unconnected-(U9-PA13-Pad40)") (class "Default")
      (node (ref "U9") (pin "40") (pinfunction "PA13_40") (pintype "bidirectional"))
    )
    (net (code "87") (name "unconnected-(U9-PA14-Pad41)") (class "Default")
      (node (ref "U9") (pin "41") (pinfunction "PA14_41") (pintype "bidirectional"))
    )
    (net (code "88") (name "unconnected-(U9-PA16-Pad43)") (class "Default")
      (node (ref "U9") (pin "43") (pinfunction "PA16_43") (pintype "bidirectional"))
    )
    (net (code "89") (name "unconnected-(U9-PA17-Pad44)") (class "Default")
      (node (ref "U9") (pin "44") (pinfunction "PA17_44") (pintype "bidirectional"))
    )
    (net (code "90") (name "unconnected-(U9-PA21-Pad55)") (class "Default")
      (node (ref "U9") (pin "55") (pinfunction "PA21_55") (pintype "bidirectional"))
    )
    (net (code "91") (name "unconnected-(U9-PA22-Pad56)") (class "Default")
      (node (ref "U9") (pin "56") (pinfunction "PA22_56") (pintype "bidirectional"))
    )
    (net (code "92") (name "unconnected-(U9-PB12-Pad53)") (class "Default")
      (node (ref "U9") (pin "53") (pinfunction "PB12_53") (pintype "bidirectional"))
    )
    (net (code "93") (name "unconnected-(U9-PB13-Pad54)") (class "Default")
      (node (ref "U9") (pin "54") (pinfunction "PB13_54") (pintype "bidirectional"))
    )
    (net (code "94") (name "unconnected-(U9-XIN32-Pad17)") (class "Default")
      (node (ref "U9") (pin "17") (pinfunction "XIN32_17") (pintype "bidirectional"))
    )
    (net (code "95") (name "unconnected-(U9-XOUT32-Pad18)") (class "Default")
      (node (ref "U9") (pin "18") (pinfunction "XOUT32_18") (pintype "bidirectional"))
    )
    (net (code "96") (name "~{AUDIO_RESET}") (class "Default")
      (node (ref "J2") (pin "20") (pinfunction "DBG_~{RESET}_20") (pintype "bidirectional"))
      (node (ref "J3") (pin "3") (pinfunction "~{RESET}_3") (pintype "bidirectional"))
      (node (ref "S1") (pin "2") (pinfunction "P$2_2") (pintype "passive"))
      (node (ref "U9") (pin "4") (pinfunction "~{RESET}_4") (pintype "bidirectional"))
    )
    (net (code "97") (name "~{FLASH_CS}") (class "Default")
      (node (ref "!CS") (pin "TESTPOINT") (pinfunction "TESTPOINT_TESTPOINT") (pintype "bidirectional"))
      (node (ref "U1") (pin "P4") (pinfunction "~{CS}_P4") (pintype "bidirectional"))
      (node (ref "U9") (pin "42") (pinfunction "PA15_42") (pintype "bidirectional"))
    )
    (net (code "98") (name "~{FLASH_RESET}") (class "Default")
      (node (ref "U1") (pin "P3") (pinfunction "~{RESET}_P3") (pintype "bidirectional"))
      (node (ref "U9") (pin "48") (pinfunction "PB11_48") (pintype "bidirectional"))
    )
  )
)
